# CLOCK.net
KiCad netlist of a schematic drawn in Altium Designer
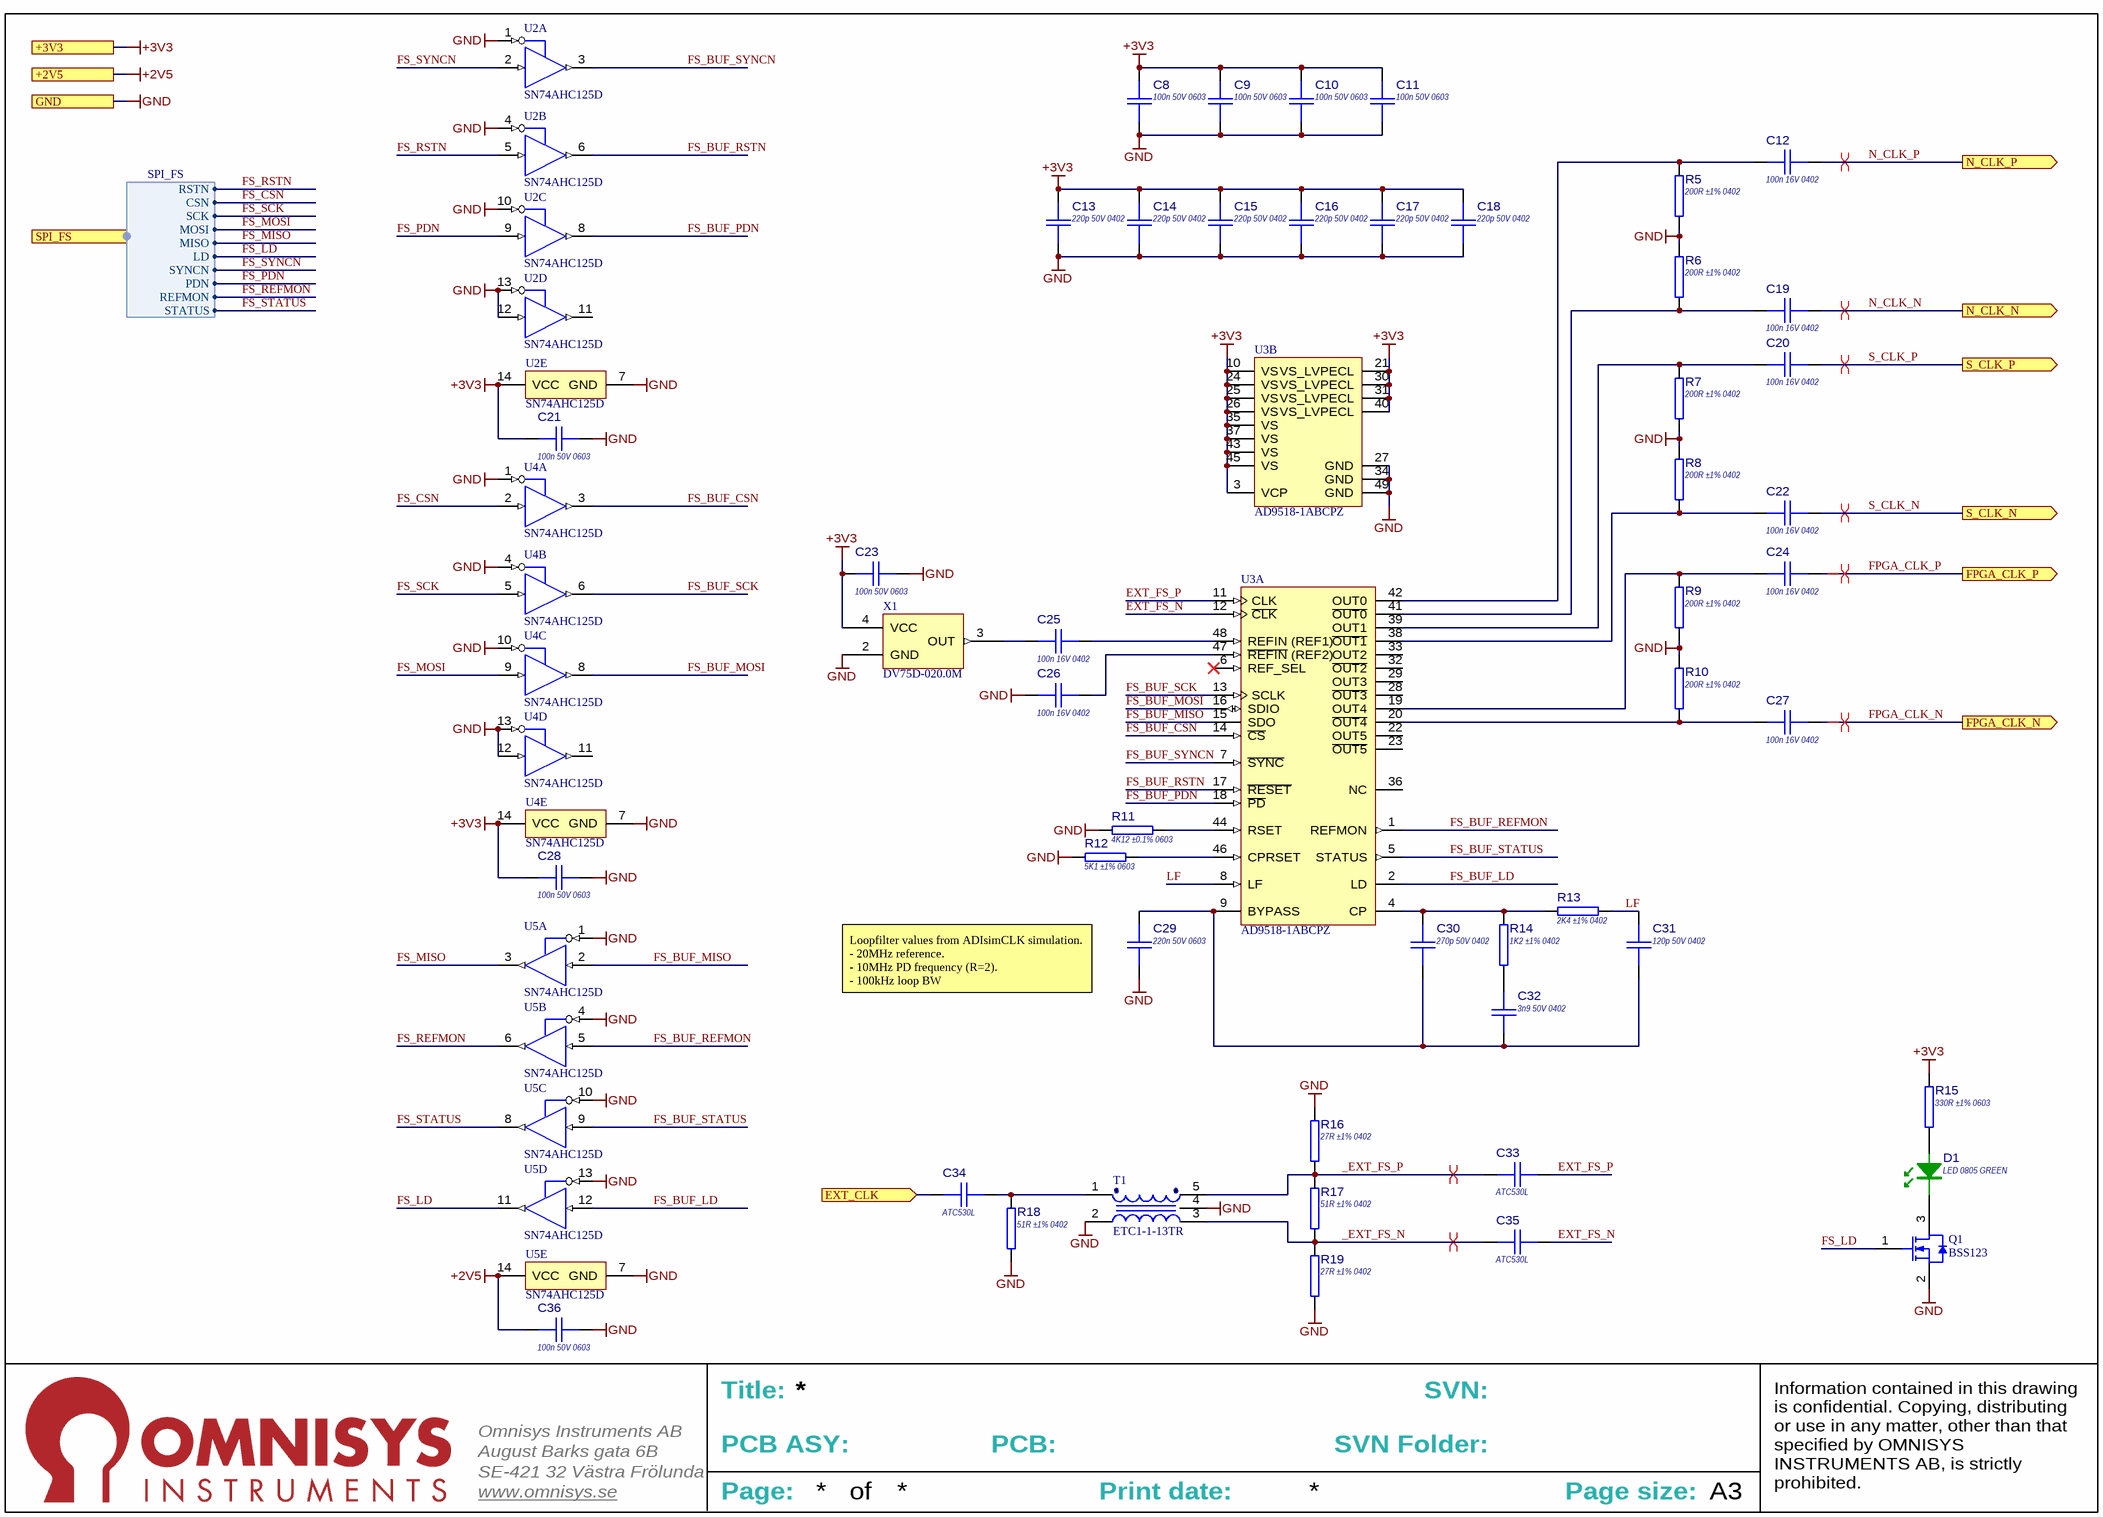
[diagram p0: CLOCK.SchDoc]

(export (version "E")
  (design (tool "Eeschema 10.0.6"))
  (components
    (comp (ref "C8")
      (value "100n 50V 0603")
      (footprint "CAPC1608X90N")
      (description "100n 50V X7R ±10% 0603 (1608 metric)")
      (fields (field (name "PARTNUMBER") "GRM188R71H104KA93") (field (name "TOLERANCE") "±10%"))
      (libsource (lib "Omnisys Vault") (part "CAP-2PIN"))
    )
    (comp (ref "C9")
      (value "100n 50V 0603")
      (footprint "CAPC1608X90N")
      (description "100n 50V X7R ±10% 0603 (1608 metric)")
      (fields (field (name "PARTNUMBER") "GRM188R71H104KA93") (field (name "TOLERANCE") "±10%"))
      (libsource (lib "Omnisys Vault") (part "CAP-2PIN"))
    )
    (comp (ref "C10")
      (value "100n 50V 0603")
      (footprint "CAPC1608X90N")
      (description "100n 50V X7R ±10% 0603 (1608 metric)")
      (fields (field (name "PARTNUMBER") "GRM188R71H104KA93") (field (name "TOLERANCE") "±10%"))
      (libsource (lib "Omnisys Vault") (part "CAP-2PIN"))
    )
    (comp (ref "C11")
      (value "100n 50V 0603")
      (footprint "CAPC1608X90N")
      (description "100n 50V X7R ±10% 0603 (1608 metric)")
      (fields (field (name "PARTNUMBER") "GRM188R71H104KA93") (field (name "TOLERANCE") "±10%"))
      (libsource (lib "Omnisys Vault") (part "CAP-2PIN"))
    )
    (comp (ref "C12")
      (value "100n 16V 0402")
      (footprint "CAPC1005X55L")
      (description "100n 16V X7R ±10% 0402 (1005 metric)")
      (fields (field (name "PARTNUMBER") "GRM155R71C104KA88") (field (name "TOLERANCE") "10%"))
      (libsource (lib "Omnisys Vault") (part "CAP-2PIN"))
    )
    (comp (ref "C13")
      (value "220p 50V 0402")
      (footprint "CAPC1005X55N")
      (description "220p 50V X7R ±10% 0402 (1005 metric)")
      (fields (field (name "PARTNUMBER") "GRM155R71H221KA01") (field (name "TOLERANCE") "10%"))
      (libsource (lib "Omnisys Vault") (part "CAP-2PIN"))
    )
    (comp (ref "C14")
      (value "220p 50V 0402")
      (footprint "CAPC1005X55N")
      (description "220p 50V X7R ±10% 0402 (1005 metric)")
      (fields (field (name "PARTNUMBER") "GRM155R71H221KA01") (field (name "TOLERANCE") "10%"))
      (libsource (lib "Omnisys Vault") (part "CAP-2PIN"))
    )
    (comp (ref "C15")
      (value "220p 50V 0402")
      (footprint "CAPC1005X55N")
      (description "220p 50V X7R ±10% 0402 (1005 metric)")
      (fields (field (name "PARTNUMBER") "GRM155R71H221KA01") (field (name "TOLERANCE") "10%"))
      (libsource (lib "Omnisys Vault") (part "CAP-2PIN"))
    )
    (comp (ref "C16")
      (value "220p 50V 0402")
      (footprint "CAPC1005X55N")
      (description "220p 50V X7R ±10% 0402 (1005 metric)")
      (fields (field (name "PARTNUMBER") "GRM155R71H221KA01") (field (name "TOLERANCE") "10%"))
      (libsource (lib "Omnisys Vault") (part "CAP-2PIN"))
    )
    (comp (ref "C17")
      (value "220p 50V 0402")
      (footprint "CAPC1005X55N")
      (description "220p 50V X7R ±10% 0402 (1005 metric)")
      (fields (field (name "PARTNUMBER") "GRM155R71H221KA01") (field (name "TOLERANCE") "10%"))
      (libsource (lib "Omnisys Vault") (part "CAP-2PIN"))
    )
    (comp (ref "C18")
      (value "220p 50V 0402")
      (footprint "CAPC1005X55N")
      (description "220p 50V X7R ±10% 0402 (1005 metric)")
      (fields (field (name "PARTNUMBER") "GRM155R71H221KA01") (field (name "TOLERANCE") "10%"))
      (libsource (lib "Omnisys Vault") (part "CAP-2PIN"))
    )
    (comp (ref "C19")
      (value "100n 16V 0402")
      (footprint "CAPC1005X55L")
      (description "100n 16V X7R ±10% 0402 (1005 metric)")
      (fields (field (name "PARTNUMBER") "GRM155R71C104KA88") (field (name "TOLERANCE") "10%"))
      (libsource (lib "Omnisys Vault") (part "CAP-2PIN"))
    )
    (comp (ref "C20")
      (value "100n 16V 0402")
      (footprint "CAPC1005X55L")
      (description "100n 16V X7R ±10% 0402 (1005 metric)")
      (fields (field (name "PARTNUMBER") "GRM155R71C104KA88") (field (name "TOLERANCE") "10%"))
      (libsource (lib "Omnisys Vault") (part "CAP-2PIN"))
    )
    (comp (ref "C21")
      (value "100n 50V 0603")
      (footprint "CAPC1608X90N")
      (description "100n 50V X7R ±10% 0603 (1608 metric)")
      (fields (field (name "PARTNUMBER") "GRM188R71H104KA93") (field (name "TOLERANCE") "±10%"))
      (libsource (lib "Omnisys Vault") (part "CAP-2PIN"))
    )
    (comp (ref "C22")
      (value "100n 16V 0402")
      (footprint "CAPC1005X55L")
      (description "100n 16V X7R ±10% 0402 (1005 metric)")
      (fields (field (name "PARTNUMBER") "GRM155R71C104KA88") (field (name "TOLERANCE") "10%"))
      (libsource (lib "Omnisys Vault") (part "CAP-2PIN"))
    )
    (comp (ref "C23")
      (value "100n 50V 0603")
      (footprint "CAPC1608X90N")
      (description "100n 50V X7R ±10% 0603 (1608 metric)")
      (fields (field (name "PARTNUMBER") "GRM188R71H104KA93") (field (name "TOLERANCE") "±10%"))
      (libsource (lib "Omnisys Vault") (part "CAP-2PIN"))
    )
    (comp (ref "C24")
      (value "100n 16V 0402")
      (footprint "CAPC1005X55L")
      (description "100n 16V X7R ±10% 0402 (1005 metric)")
      (fields (field (name "PARTNUMBER") "GRM155R71C104KA88") (field (name "TOLERANCE") "10%"))
      (libsource (lib "Omnisys Vault") (part "CAP-2PIN"))
    )
    (comp (ref "C25")
      (value "100n 16V 0402")
      (footprint "CAPC1005X55L")
      (description "100n 16V X7R ±10% 0402 (1005 metric)")
      (fields (field (name "PARTNUMBER") "GRM155R71C104KA88") (field (name "TOLERANCE") "10%"))
      (libsource (lib "Omnisys Vault") (part "CAP-2PIN"))
    )
    (comp (ref "C26")
      (value "100n 16V 0402")
      (footprint "CAPC1005X55L")
      (description "100n 16V X7R ±10% 0402 (1005 metric)")
      (fields (field (name "PARTNUMBER") "GRM155R71C104KA88") (field (name "TOLERANCE") "10%"))
      (libsource (lib "Omnisys Vault") (part "CAP-2PIN"))
    )
    (comp (ref "C27")
      (value "100n 16V 0402")
      (footprint "CAPC1005X55L")
      (description "100n 16V X7R ±10% 0402 (1005 metric)")
      (fields (field (name "PARTNUMBER") "GRM155R71C104KA88") (field (name "TOLERANCE") "10%"))
      (libsource (lib "Omnisys Vault") (part "CAP-2PIN"))
    )
    (comp (ref "C28")
      (value "100n 50V 0603")
      (footprint "CAPC1608X90N")
      (description "100n 50V X7R ±10% 0603 (1608 metric)")
      (fields (field (name "PARTNUMBER") "GRM188R71H104KA93") (field (name "TOLERANCE") "±10%"))
      (libsource (lib "Omnisys Vault") (part "CAP-2PIN"))
    )
    (comp (ref "C29")
      (value "220n 50V 0603")
      (footprint "CAPC1608X90L")
      (description "220n 50V X7R ±10% 0603 (1608 metric)")
      (fields (field (name "PARTNUMBER") "GRM188R71H224KAC4") (field (name "TOLERANCE") "±10%"))
      (libsource (lib "Omnisys Vault") (part "CAP-2PIN"))
    )
    (comp (ref "C30")
      (value "270p 50V 0402")
      (footprint "CAPC1005X55L")
      (description "270p 50V X7R ±10% 0402 (1005 metric)")
      (fields (field (name "PARTNUMBER") "GRM155R71H271KA01") (field (name "TOLERANCE") "10%"))
      (libsource (lib "Omnisys Vault") (part "CAP-2PIN"))
    )
    (comp (ref "C31")
      (value "120p 50V 0402")
      (footprint "CAPC1005X55L")
      (description "120p 50V C0G ±2% 0402 (1005 metric)")
      (fields (field (name "PARTNUMBER") "GRM1555C1H121GA01") (field (name "TOLERANCE") "2%"))
      (libsource (lib "Omnisys Vault") (part "CAP-2PIN"))
    )
    (comp (ref "C32")
      (value "3n9 50V 0402")
      (footprint "CAPC1005X55L")
      (description "3n9 50V X7R ±10% 0402 (1005 metric)")
      (fields (field (name "PARTNUMBER") "GRM155R71H392KA01") (field (name "TOLERANCE") "10%"))
      (libsource (lib "Omnisys Vault") (part "CAP-2PIN"))
    )
    (comp (ref "C33")
      (value "ATC530L")
      (footprint "CAPC1005X06L")
      (description "100n 16V ±15% 0402 (1005 metric) ATC530L104KT16T")
      (fields (field (name "TOLERANCE") "±15%"))
      (libsource (lib "Omnisys Vault") (part "CAP-2PIN"))
    )
    (comp (ref "C34")
      (value "ATC530L")
      (footprint "CAPC1005X06L")
      (description "100n 16V ±15% 0402 (1005 metric) ATC530L104KT16T")
      (fields (field (name "TOLERANCE") "±15%"))
      (libsource (lib "Omnisys Vault") (part "CAP-2PIN"))
    )
    (comp (ref "C35")
      (value "ATC530L")
      (footprint "CAPC1005X06L")
      (description "100n 16V ±15% 0402 (1005 metric) ATC530L104KT16T")
      (fields (field (name "TOLERANCE") "±15%"))
      (libsource (lib "Omnisys Vault") (part "CAP-2PIN"))
    )
    (comp (ref "C36")
      (value "100n 50V 0603")
      (footprint "CAPC1608X90N")
      (description "100n 50V X7R ±10% 0603 (1608 metric)")
      (fields (field (name "PARTNUMBER") "GRM188R71H104KA93") (field (name "TOLERANCE") "±10%"))
      (libsource (lib "Omnisys Vault") (part "CAP-2PIN"))
    )
    (comp (ref "D1")
      (value "LED 0805 GREEN")
      (footprint "LED2012-GREEN")
      (libsource (lib "Omnisys Vault") (part "LED-2PIN-GREEN"))
    )
    (comp (ref "Q1")
      (value "BSS123")
      (footprint "FAIR-SOT23-3_V")
      (fields (field (name "MANUFACTURER") "Fairchild"))
      (libsource (lib "Altium Content Vault") (part "NEMOS-GSD-3"))
    )
    (comp (ref "R5")
      (value "200R ±1% 0402")
      (footprint "RESC1005L")
      (description "200R ±1% ±100 ppm/˚C 0.05W 50V 0402 (1005 metric)")
      (fields (field (name "POWER") "0.10W") (field (name "TOLERANCE") "1"))
      (libsource (lib "Omnisys Vault") (part "RES-2PIN"))
    )
    (comp (ref "R6")
      (value "200R ±1% 0402")
      (footprint "RESC1005L")
      (description "200R ±1% ±100 ppm/˚C 0.05W 50V 0402 (1005 metric)")
      (fields (field (name "POWER") "0.10W") (field (name "TOLERANCE") "1"))
      (libsource (lib "Omnisys Vault") (part "RES-2PIN"))
    )
    (comp (ref "R7")
      (value "200R ±1% 0402")
      (footprint "RESC1005L")
      (description "200R ±1% ±100 ppm/˚C 0.05W 50V 0402 (1005 metric)")
      (fields (field (name "POWER") "0.10W") (field (name "TOLERANCE") "1"))
      (libsource (lib "Omnisys Vault") (part "RES-2PIN"))
    )
    (comp (ref "R8")
      (value "200R ±1% 0402")
      (footprint "RESC1005L")
      (description "200R ±1% ±100 ppm/˚C 0.05W 50V 0402 (1005 metric)")
      (fields (field (name "POWER") "0.10W") (field (name "TOLERANCE") "1"))
      (libsource (lib "Omnisys Vault") (part "RES-2PIN"))
    )
    (comp (ref "R9")
      (value "200R ±1% 0402")
      (footprint "RESC1005L")
      (description "200R ±1% ±100 ppm/˚C 0.05W 50V 0402 (1005 metric)")
      (fields (field (name "POWER") "0.10W") (field (name "TOLERANCE") "1"))
      (libsource (lib "Omnisys Vault") (part "RES-2PIN"))
    )
    (comp (ref "R10")
      (value "200R ±1% 0402")
      (footprint "RESC1005L")
      (description "200R ±1% ±100 ppm/˚C 0.05W 50V 0402 (1005 metric)")
      (fields (field (name "POWER") "0.10W") (field (name "TOLERANCE") "1"))
      (libsource (lib "Omnisys Vault") (part "RES-2PIN"))
    )
    (comp (ref "R11")
      (value "4K12 ±0.1% 0603")
      (footprint "RESC1608N")
      (description "4K12 ±0.1% ±15 ppm/˚C 0.1W 50V 0603 (1608 metric) Thinfilm")
      (fields (field (name "POWER") "0.1W") (field (name "TOLERANCE") "±0.1"))
      (libsource (lib "Omnisys Vault") (part "RES-2PIN"))
    )
    (comp (ref "R12")
      (value "5K1 ±1% 0603")
      (footprint "RESC1608N")
      (description "5K1 ±1% ±100 ppm/˚C 0.10W 75V 0603 (1608 metric)")
      (fields (field (name "POWER") "100mW") (field (name "TOLERANCE") "1%"))
      (libsource (lib "Omnisys Vault") (part "RES-2PIN"))
    )
    (comp (ref "R13")
      (value "2K4 ±1% 0402")
      (footprint "RESC1005L")
      (description "2K4 ±1% ±100 ppm/˚C 0.05W 50V 0402 (1005 metric)")
      (fields (field (name "POWER") "0.10W") (field (name "TOLERANCE") "1"))
      (libsource (lib "Omnisys Vault") (part "RES-2PIN"))
    )
    (comp (ref "R14")
      (value "1K2 ±1% 0402")
      (footprint "RESC1005L")
      (description "1K2 ±1% ±100 ppm/˚C 0.05W 50V 0402 (1005 metric)")
      (fields (field (name "POWER") "0.10W") (field (name "TOLERANCE") "1"))
      (libsource (lib "Omnisys Vault") (part "RES-2PIN"))
    )
    (comp (ref "R15")
      (value "330R ±1% 0603")
      (footprint "RESC1608N")
      (description "330R ±1% ±100 ppm/˚C 0.10W 75V 0603 (1608 metric)")
      (fields (field (name "POWER") "100mW") (field (name "TOLERANCE") "1%"))
      (libsource (lib "Omnisys Vault") (part "RES-2PIN"))
    )
    (comp (ref "R16")
      (value "27R ±1% 0402")
      (footprint "RESC1005L")
      (description "27R ±1% ±100 ppm/˚C 0.05W 50V 0402 (1005 metric)")
      (fields (field (name "POWER") "0.10W") (field (name "TOLERANCE") "1"))
      (libsource (lib "Omnisys Vault") (part "RES-2PIN"))
    )
    (comp (ref "R17")
      (value "51R ±1% 0402")
      (footprint "RESC1005L")
      (description "51R ±1% ±100 ppm/˚C 0.05W 50V 0402 (1005 metric)")
      (fields (field (name "POWER") "0.10W") (field (name "TOLERANCE") "1"))
      (libsource (lib "Omnisys Vault") (part "RES-2PIN"))
    )
    (comp (ref "R18")
      (value "51R ±1% 0402")
      (footprint "RESC1005L")
      (description "51R ±1% ±100 ppm/˚C 0.05W 50V 0402 (1005 metric)")
      (fields (field (name "POWER") "0.10W") (field (name "TOLERANCE") "1"))
      (libsource (lib "Omnisys Vault") (part "RES-2PIN"))
    )
    (comp (ref "R19")
      (value "27R ±1% 0402")
      (footprint "RESC1005L")
      (description "27R ±1% ±100 ppm/˚C 0.05W 50V 0402 (1005 metric)")
      (fields (field (name "POWER") "0.10W") (field (name "TOLERANCE") "1"))
      (libsource (lib "Omnisys Vault") (part "RES-2PIN"))
    )
    (comp (ref "T1")
      (value "ETC1-1-13TR")
      (footprint "SOTFL50P160X73-3N")
      (description "Transformers Audio & Signal 4.5-3000MHz IL 2dB Impedance Ratio 1:1")
      (libsource (lib "Omnisys Vault") (part "ETC1-1-13TR"))
    )
    (comp (ref "U2")
      (value "SN74AHC125D")
      (footprint "SOIC127P600X175-14N")
      (description "Buffer/Line Driver 4-CH Non-Inverting 3-ST CMOS 14-Pin SOIC Tube")
      (libsource (lib "Omnisys Vault") (part "SN74AHC125D"))
    )
    (comp (ref "U3")
      (value "AD9518-1ABCPZ")
      (footprint "ADI-CP-48-8_M")
      (fields (field (name "MANUFACTURER") "Analog Devices"))
      (libsource (lib "Altium Content Vault") (part "ADI-AD9518-1-CP-48-8"))
    )
    (comp (ref "U4")
      (value "SN74AHC125D")
      (footprint "SOIC127P600X175-14N")
      (description "Buffer/Line Driver 4-CH Non-Inverting 3-ST CMOS 14-Pin SOIC Tube")
      (libsource (lib "Omnisys Vault") (part "SN74AHC125D"))
    )
    (comp (ref "U5")
      (value "SN74AHC125D")
      (footprint "SOIC127P600X175-14N")
      (description "Buffer/Line Driver 4-CH Non-Inverting 3-ST CMOS 14-Pin SOIC Tube")
      (libsource (lib "") (part "SN74AHC125D_1"))
    )
    (comp (ref "X1")
      (value "DV75D-020.0M")
      (footprint "SON127P420X200-4N")
      (description "OSC TCXO 20.000MHZ LVCMOS SMD")
      (libsource (lib "Omnisys Vault") (part "DV75D-020.0M"))
    )
  )
  (nets
    (net (code "2") (name "+2V5") (class "Default")
      (node (ref "C36") (pin "2") (pinfunction "2_2") (pintype "passive"))
      (node (ref "U5") (pin "14") (pinfunction "VCC_14") (pintype "power_in"))
    )
    (net (code "3") (name "+3V3") (class "Default")
      (node (ref "C10") (pin "2") (pinfunction "2_2") (pintype "passive"))
      (node (ref "C11") (pin "2") (pinfunction "2_2") (pintype "passive"))
      (node (ref "C13") (pin "2") (pinfunction "2_2") (pintype "passive"))
      (node (ref "C14") (pin "2") (pinfunction "2_2") (pintype "passive"))
      (node (ref "C15") (pin "2") (pinfunction "2_2") (pintype "passive"))
      (node (ref "C16") (pin "2") (pinfunction "2_2") (pintype "passive"))
      (node (ref "C17") (pin "2") (pinfunction "2_2") (pintype "passive"))
      (node (ref "C18") (pin "2") (pinfunction "2_2") (pintype "passive"))
      (node (ref "C21") (pin "2") (pinfunction "2_2") (pintype "passive"))
      (node (ref "C23") (pin "2") (pinfunction "2_2") (pintype "passive"))
      (node (ref "C28") (pin "2") (pinfunction "2_2") (pintype "passive"))
      (node (ref "C8") (pin "2") (pinfunction "2_2") (pintype "passive"))
      (node (ref "C9") (pin "2") (pinfunction "2_2") (pintype "passive"))
      (node (ref "R15") (pin "2") (pinfunction "2_2") (pintype "passive"))
      (node (ref "U2") (pin "14") (pinfunction "VCC_14") (pintype "power_in"))
      (node (ref "U3") (pin "10") (pinfunction "VS_10") (pintype "power_in"))
      (node (ref "U3") (pin "21") (pinfunction "VS_LVPECL_21") (pintype "power_in"))
      (node (ref "U3") (pin "24") (pinfunction "VS_24") (pintype "power_in"))
      (node (ref "U3") (pin "25") (pinfunction "VS_25") (pintype "power_in"))
      (node (ref "U3") (pin "26") (pinfunction "VS_26") (pintype "power_in"))
      (node (ref "U3") (pin "3") (pinfunction "VCP_3") (pintype "power_in"))
      (node (ref "U3") (pin "30") (pinfunction "VS_LVPECL_30") (pintype "power_in"))
      (node (ref "U3") (pin "31") (pinfunction "VS_LVPECL_31") (pintype "power_in"))
      (node (ref "U3") (pin "35") (pinfunction "VS_35") (pintype "power_in"))
      (node (ref "U3") (pin "37") (pinfunction "VS_37") (pintype "power_in"))
      (node (ref "U3") (pin "40") (pinfunction "VS_LVPECL_40") (pintype "power_in"))
      (node (ref "U3") (pin "43") (pinfunction "VS_43") (pintype "power_in"))
      (node (ref "U3") (pin "45") (pinfunction "VS_45") (pintype "power_in"))
      (node (ref "U4") (pin "14") (pinfunction "VCC_14") (pintype "power_in"))
      (node (ref "X1") (pin "4") (pinfunction "VCC_4") (pintype "power_in"))
    )
    (net (code "4") (name "/EXT_CLK") (class "Default")
      (node (ref "C34") (pin "1") (pinfunction "1_1") (pintype "passive"))
    )
    (net (code "5") (name "/EXT_FS_N") (class "Default")
      (node (ref "C35") (pin "2") (pinfunction "2_2") (pintype "passive"))
      (node (ref "U3") (pin "12") (pinfunction "~{CLK}_12") (pintype "input"))
    )
    (net (code "6") (name "/EXT_FS_P") (class "Default")
      (node (ref "C33") (pin "2") (pinfunction "2_2") (pintype "passive"))
      (node (ref "U3") (pin "11") (pinfunction "CLK_11") (pintype "input"))
    )
    (net (code "7") (name "/FPGA_CLK_N") (class "Default")
      (node (ref "C27") (pin "1") (pinfunction "1_1") (pintype "passive"))
    )
    (net (code "8") (name "/FPGA_CLK_P") (class "Default")
      (node (ref "C24") (pin "1") (pinfunction "1_1") (pintype "passive"))
    )
    (net (code "9") (name "/FS_BUF_CSN") (class "Default")
      (node (ref "U3") (pin "14") (pinfunction "~{CS}_14") (pintype "input"))
      (node (ref "U4") (pin "3") (pinfunction "1Y_3") (pintype "output"))
    )
    (net (code "10") (name "/FS_BUF_LD") (class "Default")
      (node (ref "U3") (pin "2") (pinfunction "LD_2") (pintype "tri_state"))
      (node (ref "U5") (pin "12") (pinfunction "4A_12") (pintype "input"))
    )
    (net (code "11") (name "/FS_BUF_MISO") (class "Default")
      (node (ref "U3") (pin "15") (pinfunction "SDO_15") (pintype "tri_state"))
      (node (ref "U5") (pin "2") (pinfunction "1A_2") (pintype "input"))
    )
    (net (code "12") (name "/FS_BUF_MOSI") (class "Default")
      (node (ref "U3") (pin "16") (pinfunction "SDIO_16") (pintype "bidirectional"))
      (node (ref "U4") (pin "8") (pinfunction "3Y_8") (pintype "output"))
    )
    (net (code "13") (name "/FS_BUF_PDN") (class "Default")
      (node (ref "U2") (pin "8") (pinfunction "3Y_8") (pintype "output"))
      (node (ref "U3") (pin "18") (pinfunction "~{PD}_18") (pintype "input"))
    )
    (net (code "14") (name "/FS_BUF_REFMON") (class "Default")
      (node (ref "U3") (pin "1") (pinfunction "REFMON_1") (pintype "output"))
      (node (ref "U5") (pin "5") (pinfunction "2A_5") (pintype "input"))
    )
    (net (code "15") (name "/FS_BUF_RSTN") (class "Default")
      (node (ref "U2") (pin "6") (pinfunction "2Y_6") (pintype "output"))
      (node (ref "U3") (pin "17") (pinfunction "~{RESET}_17") (pintype "input"))
    )
    (net (code "16") (name "/FS_BUF_SCK") (class "Default")
      (node (ref "U3") (pin "13") (pinfunction "SCLK_13") (pintype "input"))
      (node (ref "U4") (pin "6") (pinfunction "2Y_6") (pintype "output"))
    )
    (net (code "17") (name "/FS_BUF_STATUS") (class "Default")
      (node (ref "U3") (pin "5") (pinfunction "STATUS_5") (pintype "output"))
      (node (ref "U5") (pin "9") (pinfunction "3A_9") (pintype "input"))
    )
    (net (code "18") (name "/FS_BUF_SYNCN") (class "Default")
      (node (ref "U2") (pin "3") (pinfunction "1Y_3") (pintype "output"))
      (node (ref "U3") (pin "7") (pinfunction "~{SYNC}_7") (pintype "input"))
    )
    (net (code "19") (name "/FS_CSN") (class "Default")
      (node (ref "U4") (pin "2") (pinfunction "1A_2") (pintype "input"))
    )
    (net (code "20") (name "/FS_LD") (class "Default")
      (node (ref "Q1") (pin "1") (pinfunction "G_1") (pintype "passive"))
      (node (ref "U5") (pin "11") (pinfunction "4Y_11") (pintype "output"))
    )
    (net (code "21") (name "/FS_MISO") (class "Default")
      (node (ref "U5") (pin "3") (pinfunction "1Y_3") (pintype "output"))
    )
    (net (code "22") (name "/FS_MOSI") (class "Default")
      (node (ref "U4") (pin "9") (pinfunction "3A_9") (pintype "input"))
    )
    (net (code "23") (name "/FS_PDN") (class "Default")
      (node (ref "U2") (pin "9") (pinfunction "3A_9") (pintype "input"))
    )
    (net (code "24") (name "/FS_REFMON") (class "Default")
      (node (ref "U5") (pin "6") (pinfunction "2Y_6") (pintype "output"))
    )
    (net (code "25") (name "/FS_RSTN") (class "Default")
      (node (ref "U2") (pin "5") (pinfunction "2A_5") (pintype "input"))
    )
    (net (code "26") (name "/FS_SCK") (class "Default")
      (node (ref "U4") (pin "5") (pinfunction "2A_5") (pintype "input"))
    )
    (net (code "27") (name "/FS_STATUS") (class "Default")
      (node (ref "U5") (pin "8") (pinfunction "3Y_8") (pintype "output"))
    )
    (net (code "28") (name "/FS_SYNCN") (class "Default")
      (node (ref "U2") (pin "2") (pinfunction "1A_2") (pintype "input"))
    )
    (net (code "29") (name "/LF") (class "Default")
      (node (ref "C31") (pin "2") (pinfunction "2_2") (pintype "passive"))
      (node (ref "R13") (pin "2") (pinfunction "2_2") (pintype "passive"))
      (node (ref "U3") (pin "8") (pinfunction "LF_8") (pintype "input"))
    )
    (net (code "30") (name "/N_CLK_N") (class "Default")
      (node (ref "C19") (pin "1") (pinfunction "1_1") (pintype "passive"))
    )
    (net (code "31") (name "/N_CLK_P") (class "Default")
      (node (ref "C12") (pin "1") (pinfunction "1_1") (pintype "passive"))
    )
    (net (code "32") (name "/S_CLK_N") (class "Default")
      (node (ref "C22") (pin "1") (pinfunction "1_1") (pintype "passive"))
    )
    (net (code "33") (name "/S_CLK_P") (class "Default")
      (node (ref "C20") (pin "1") (pinfunction "1_1") (pintype "passive"))
    )
    (net (code "34") (name "/_EXT_FS_N") (class "Default")
      (node (ref "C35") (pin "1") (pinfunction "1_1") (pintype "passive"))
      (node (ref "R17") (pin "1") (pinfunction "1_1") (pintype "passive"))
      (node (ref "R19") (pin "1") (pinfunction "1_1") (pintype "passive"))
      (node (ref "T1") (pin "3") (pinfunction "Secondary_3") (pintype "passive"))
    )
    (net (code "35") (name "/_EXT_FS_P") (class "Default")
      (node (ref "C33") (pin "1") (pinfunction "1_1") (pintype "passive"))
      (node (ref "R16") (pin "1") (pinfunction "1_1") (pintype "passive"))
      (node (ref "R17") (pin "2") (pinfunction "2_2") (pintype "passive"))
      (node (ref "T1") (pin "5") (pinfunction "Secondary_dot_5") (pintype "passive"))
    )
    (net (code "37") (name "GND") (class "Default")
      (node (ref "C10") (pin "1") (pinfunction "1_1") (pintype "passive"))
      (node (ref "C11") (pin "1") (pinfunction "1_1") (pintype "passive"))
      (node (ref "C13") (pin "1") (pinfunction "1_1") (pintype "passive"))
      (node (ref "C14") (pin "1") (pinfunction "1_1") (pintype "passive"))
      (node (ref "C15") (pin "1") (pinfunction "1_1") (pintype "passive"))
      (node (ref "C16") (pin "1") (pinfunction "1_1") (pintype "passive"))
      (node (ref "C17") (pin "1") (pinfunction "1_1") (pintype "passive"))
      (node (ref "C18") (pin "1") (pinfunction "1_1") (pintype "passive"))
      (node (ref "C21") (pin "1") (pinfunction "1_1") (pintype "passive"))
      (node (ref "C23") (pin "1") (pinfunction "1_1") (pintype "passive"))
      (node (ref "C26") (pin "2") (pinfunction "2_2") (pintype "passive"))
      (node (ref "C28") (pin "1") (pinfunction "1_1") (pintype "passive"))
      (node (ref "C29") (pin "2") (pinfunction "2_2") (pintype "passive"))
      (node (ref "C36") (pin "1") (pinfunction "1_1") (pintype "passive"))
      (node (ref "C8") (pin "1") (pinfunction "1_1") (pintype "passive"))
      (node (ref "C9") (pin "1") (pinfunction "1_1") (pintype "passive"))
      (node (ref "Q1") (pin "2") (pinfunction "S_2") (pintype "passive"))
      (node (ref "R10") (pin "2") (pinfunction "2_2") (pintype "passive"))
      (node (ref "R11") (pin "1") (pinfunction "1_1") (pintype "passive"))
      (node (ref "R12") (pin "1") (pinfunction "1_1") (pintype "passive"))
      (node (ref "R16") (pin "2") (pinfunction "2_2") (pintype "passive"))
      (node (ref "R18") (pin "2") (pinfunction "2_2") (pintype "passive"))
      (node (ref "R19") (pin "2") (pinfunction "2_2") (pintype "passive"))
      (node (ref "R5") (pin "2") (pinfunction "2_2") (pintype "passive"))
      (node (ref "R6") (pin "2") (pinfunction "2_2") (pintype "passive"))
      (node (ref "R7") (pin "2") (pinfunction "2_2") (pintype "passive"))
      (node (ref "R8") (pin "2") (pinfunction "2_2") (pintype "passive"))
      (node (ref "R9") (pin "2") (pinfunction "2_2") (pintype "passive"))
      (node (ref "T1") (pin "2") (pinfunction "Primary_2") (pintype "passive"))
      (node (ref "T1") (pin "4") (pinfunction "NC_4") (pintype "passive"))
      (node (ref "U2") (pin "1") (pinfunction "1OE#_1") (pintype "input"))
      (node (ref "U2") (pin "10") (pinfunction "3OE#_10") (pintype "input"))
      (node (ref "U2") (pin "12") (pinfunction "4A_12") (pintype "input"))
      (node (ref "U2") (pin "13") (pinfunction "4OE#_13") (pintype "input"))
      (node (ref "U2") (pin "4") (pinfunction "2OE#_4") (pintype "input"))
      (node (ref "U2") (pin "7") (pinfunction "GND_7") (pintype "power_in"))
      (node (ref "U3") (pin "27") (pinfunction "GND_27") (pintype "power_in"))
      (node (ref "U3") (pin "34") (pinfunction "GND_34") (pintype "power_in"))
      (node (ref "U3") (pin "49") (pinfunction "GND_49") (pintype "power_in"))
      (node (ref "U4") (pin "1") (pinfunction "1OE#_1") (pintype "input"))
      (node (ref "U4") (pin "10") (pinfunction "3OE#_10") (pintype "input"))
      (node (ref "U4") (pin "12") (pinfunction "4A_12") (pintype "input"))
      (node (ref "U4") (pin "13") (pinfunction "4OE#_13") (pintype "input"))
      (node (ref "U4") (pin "4") (pinfunction "2OE#_4") (pintype "input"))
      (node (ref "U4") (pin "7") (pinfunction "GND_7") (pintype "power_in"))
      (node (ref "U5") (pin "1") (pinfunction "1OE#_1") (pintype "input"))
      (node (ref "U5") (pin "10") (pinfunction "3OE#_10") (pintype "input"))
      (node (ref "U5") (pin "13") (pinfunction "4OE#_13") (pintype "input"))
      (node (ref "U5") (pin "4") (pinfunction "2OE#_4") (pintype "input"))
      (node (ref "U5") (pin "7") (pinfunction "GND_7") (pintype "power_in"))
      (node (ref "X1") (pin "2") (pinfunction "GND_2") (pintype "power_in"))
    )
    (net (code "38") (name "Net-(C32-Pad1)") (class "Default")
      (node (ref "C32") (pin "1") (pinfunction "1_1") (pintype "passive"))
      (node (ref "R14") (pin "1") (pinfunction "1_1") (pintype "passive"))
    )
    (net (code "39") (name "Net-(D1-Pad2)") (class "Default")
      (node (ref "D1") (pin "2") (pintype "passive"))
      (node (ref "R15") (pin "1") (pinfunction "1_1") (pintype "passive"))
    )
    (net (code "40") (name "Net-(Q1-D)") (class "Default")
      (node (ref "D1") (pin "1") (pintype "passive"))
      (node (ref "Q1") (pin "3") (pinfunction "D_3") (pintype "passive"))
    )
    (net (code "41") (name "Net-(T1-Primary_dot)") (class "Default")
      (node (ref "C34") (pin "2") (pinfunction "2_2") (pintype "passive"))
      (node (ref "R18") (pin "1") (pinfunction "1_1") (pintype "passive"))
      (node (ref "T1") (pin "1") (pinfunction "Primary_dot_1") (pintype "passive"))
    )
    (net (code "42") (name "Net-(U3A-BYPASS)") (class "Default")
      (node (ref "C29") (pin "1") (pinfunction "1_1") (pintype "passive"))
      (node (ref "C30") (pin "2") (pinfunction "2_2") (pintype "passive"))
      (node (ref "C31") (pin "1") (pinfunction "1_1") (pintype "passive"))
      (node (ref "C32") (pin "2") (pinfunction "2_2") (pintype "passive"))
      (node (ref "U3") (pin "9") (pinfunction "BYPASS_9") (pintype "passive"))
    )
    (net (code "43") (name "Net-(U3A-CP)") (class "Default")
      (node (ref "C30") (pin "1") (pinfunction "1_1") (pintype "passive"))
      (node (ref "R13") (pin "1") (pinfunction "1_1") (pintype "passive"))
      (node (ref "R14") (pin "2") (pinfunction "2_2") (pintype "passive"))
      (node (ref "U3") (pin "4") (pinfunction "CP_4") (pintype "tri_state"))
    )
    (net (code "44") (name "Net-(U3A-CPRSET)") (class "Default")
      (node (ref "R12") (pin "2") (pinfunction "2_2") (pintype "passive"))
      (node (ref "U3") (pin "46") (pinfunction "CPRSET_46") (pintype "input"))
    )
    (net (code "45") (name "Net-(U3A-OUT0)") (class "Default")
      (node (ref "C12") (pin "2") (pinfunction "2_2") (pintype "passive"))
      (node (ref "R5") (pin "1") (pinfunction "1_1") (pintype "passive"))
      (node (ref "U3") (pin "42") (pinfunction "OUT0_42") (pintype "tri_state"))
    )
    (net (code "46") (name "Net-(U3A-OUT1)") (class "Default")
      (node (ref "C20") (pin "2") (pinfunction "2_2") (pintype "passive"))
      (node (ref "R7") (pin "1") (pinfunction "1_1") (pintype "passive"))
      (node (ref "U3") (pin "39") (pinfunction "OUT1_39") (pintype "tri_state"))
    )
    (net (code "47") (name "Net-(U3A-OUT4)") (class "Default")
      (node (ref "C24") (pin "2") (pinfunction "2_2") (pintype "passive"))
      (node (ref "R9") (pin "1") (pinfunction "1_1") (pintype "passive"))
      (node (ref "U3") (pin "19") (pinfunction "OUT4_19") (pintype "tri_state"))
    )
    (net (code "48") (name "Net-(U3A-REFIN_(REF1))") (class "Default")
      (node (ref "C25") (pin "1") (pinfunction "1_1") (pintype "passive"))
      (node (ref "U3") (pin "48") (pinfunction "REFIN_(REF1)_48") (pintype "input"))
    )
    (net (code "49") (name "Net-(U3A-RSET)") (class "Default")
      (node (ref "R11") (pin "2") (pinfunction "2_2") (pintype "passive"))
      (node (ref "U3") (pin "44") (pinfunction "RSET_44") (pintype "input"))
    )
    (net (code "50") (name "Net-(U3A-~{OUT0})") (class "Default")
      (node (ref "C19") (pin "2") (pinfunction "2_2") (pintype "passive"))
      (node (ref "R6") (pin "1") (pinfunction "1_1") (pintype "passive"))
      (node (ref "U3") (pin "41") (pinfunction "~{OUT0}_41") (pintype "tri_state"))
    )
    (net (code "51") (name "Net-(U3A-~{OUT1})") (class "Default")
      (node (ref "C22") (pin "2") (pinfunction "2_2") (pintype "passive"))
      (node (ref "R8") (pin "1") (pinfunction "1_1") (pintype "passive"))
      (node (ref "U3") (pin "38") (pinfunction "~{OUT1}_38") (pintype "tri_state"))
    )
    (net (code "52") (name "Net-(U3A-~{OUT4})") (class "Default")
      (node (ref "C27") (pin "2") (pinfunction "2_2") (pintype "passive"))
      (node (ref "R10") (pin "1") (pinfunction "1_1") (pintype "passive"))
      (node (ref "U3") (pin "20") (pinfunction "~{OUT4}_20") (pintype "tri_state"))
    )
    (net (code "53") (name "Net-(U3A-~{REFIN}_(REF2))") (class "Default")
      (node (ref "C26") (pin "1") (pinfunction "1_1") (pintype "passive"))
      (node (ref "U3") (pin "47") (pinfunction "~{REFIN}_(REF2)_47") (pintype "input"))
    )
    (net (code "54") (name "Net-(X1-OUT)") (class "Default")
      (node (ref "C25") (pin "2") (pinfunction "2_2") (pintype "passive"))
      (node (ref "X1") (pin "3") (pinfunction "OUT_3") (pintype "output"))
    )
    (net (code "55") (name "unconnected-(U2D-4Y-Pad11)") (class "Default")
      (node (ref "U2") (pin "11") (pinfunction "4Y_11") (pintype "output"))
    )
    (net (code "56") (name "unconnected-(U3A-NC-Pad36)") (class "Default")
      (node (ref "U3") (pin "36") (pinfunction "NC_36") (pintype "passive"))
    )
    (net (code "57") (name "unconnected-(U3A-OUT2-Pad33)") (class "Default")
      (node (ref "U3") (pin "33") (pinfunction "OUT2_33") (pintype "tri_state"))
    )
    (net (code "58") (name "unconnected-(U3A-OUT3-Pad29)") (class "Default")
      (node (ref "U3") (pin "29") (pinfunction "OUT3_29") (pintype "tri_state"))
    )
    (net (code "59") (name "unconnected-(U3A-OUT5-Pad22)") (class "Default")
      (node (ref "U3") (pin "22") (pinfunction "OUT5_22") (pintype "tri_state"))
    )
    (net (code "60") (name "unconnected-(U3A-REF_SEL-Pad6)") (class "Default")
      (node (ref "U3") (pin "6") (pinfunction "REF_SEL_6") (pintype "input+no_connect"))
    )
    (net (code "61") (name "unconnected-(U3A-~{OUT2}-Pad32)") (class "Default")
      (node (ref "U3") (pin "32") (pinfunction "~{OUT2}_32") (pintype "tri_state"))
    )
    (net (code "62") (name "unconnected-(U3A-~{OUT3}-Pad28)") (class "Default")
      (node (ref "U3") (pin "28") (pinfunction "~{OUT3}_28") (pintype "tri_state"))
    )
    (net (code "63") (name "unconnected-(U3A-~{OUT5}-Pad23)") (class "Default")
      (node (ref "U3") (pin "23") (pinfunction "~{OUT5}_23") (pintype "tri_state"))
    )
    (net (code "64") (name "unconnected-(U4D-4Y-Pad11)") (class "Default")
      (node (ref "U4") (pin "11") (pinfunction "4Y_11") (pintype "output"))
    )
  )
)
